# hud_v300_MU.net
KiCad netlist of a schematic drawn in Altium Designer
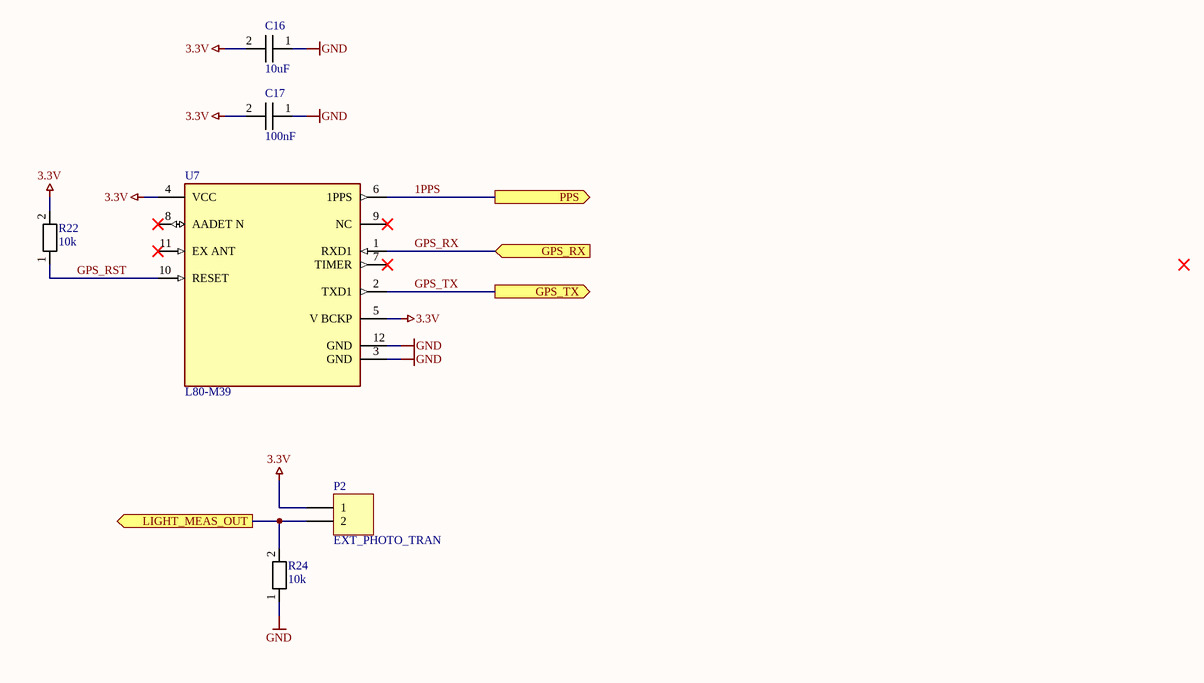
[diagram p0: hud_v300_MU.SchDoc]

(export (version "E")
  (design (tool "Eeschema 10.0.6"))
  (components
    (comp (ref "C16") (value "10uF") (footprint "1210_C") (libsource (lib "Schlib1") (part "CAPACITOR")))
    (comp (ref "C17") (value "100nF") (footprint "0805_C") (libsource (lib "Schlib1") (part "CAPACITOR")))
    (comp (ref "P2")
      (value "EXT_PHOTO_TRAN")
      (footprint "HDR1X2")
      (description "Header, 2-Pin")
      (fields (field (name "PUBLISHER") "Altium Limited"))
      (libsource (lib "Miscellaneous Connectors") (part "Header 2"))
    )
    (comp (ref "R22") (value "10k") (footprint "0805") (libsource (lib "Schlib1") (part "RESISTOR")))
    (comp (ref "R24") (value "10k") (footprint "0805") (libsource (lib "Schlib1") (part "RESISTOR")))
    (comp (ref "U7")
      (value "L80-M39")
      (footprint "L80-M39")
      (description "QUECTEL GPS MODULE")
      (libsource (lib "ic_modules") (part "L80-M39"))
    )
  )
  (nets
    (net (code "1") (name "/1PPS") (class "Default")
      (node (ref "U7") (pin "6") (pinfunction "1PPS_6") (pintype "output"))
    )
    (net (code "2") (name "/GPS_RST") (class "Default")
      (node (ref "R22") (pin "1") (pinfunction "0_1") (pintype "passive"))
      (node (ref "U7") (pin "10") (pinfunction "RESET_10") (pintype "input"))
    )
    (net (code "3") (name "/GPS_RX") (class "Default")
      (node (ref "U7") (pin "1") (pinfunction "RXD1_1") (pintype "input"))
    )
    (net (code "4") (name "/GPS_TX") (class "Default")
      (node (ref "U7") (pin "2") (pinfunction "TXD1_2") (pintype "output"))
    )
    (net (code "5") (name "/LIGHT_MEAS_OUT") (class "Default")
      (node (ref "P2") (pin "2") (pinfunction "2_2") (pintype "passive"))
      (node (ref "R24") (pin "2") (pinfunction "1_2") (pintype "passive"))
    )
    (net (code "6") (name "3.3V") (class "Default")
      (node (ref "C16") (pin "2") (pinfunction "2_2") (pintype "passive"))
      (node (ref "C17") (pin "2") (pinfunction "2_2") (pintype "passive"))
      (node (ref "P2") (pin "1") (pinfunction "1_1") (pintype "passive"))
      (node (ref "R22") (pin "2") (pinfunction "1_2") (pintype "passive"))
      (node (ref "U7") (pin "4") (pinfunction "VCC_4") (pintype "power_in"))
      (node (ref "U7") (pin "5") (pinfunction "V_BCKP_5") (pintype "power_in"))
    )
    (net (code "7") (name "GND") (class "Default")
      (node (ref "C16") (pin "1") (pinfunction "1_1") (pintype "passive"))
      (node (ref "C17") (pin "1") (pinfunction "1_1") (pintype "passive"))
      (node (ref "R24") (pin "1") (pinfunction "0_1") (pintype "passive"))
      (node (ref "U7") (pin "12") (pinfunction "GND_12") (pintype "power_in"))
      (node (ref "U7") (pin "3") (pinfunction "GND_3") (pintype "power_in"))
    )
    (net (code "8") (name "unconnected-(U7-AADET_N-Pad8)") (class "Default")
      (node (ref "U7") (pin "8") (pinfunction "AADET_N_8") (pintype "bidirectional+no_connect"))
    )
    (net (code "9") (name "unconnected-(U7-EX_ANT-Pad11)") (class "Default")
      (node (ref "U7") (pin "11") (pinfunction "EX_ANT_11") (pintype "input+no_connect"))
    )
    (net (code "10") (name "unconnected-(U7-NC-Pad9)") (class "Default")
      (node (ref "U7") (pin "9") (pinfunction "NC_9") (pintype "passive+no_connect"))
    )
    (net (code "11") (name "unconnected-(U7-TIMER-Pad7)") (class "Default")
      (node (ref "U7") (pin "7") (pinfunction "TIMER_7") (pintype "output+no_connect"))
    )
  )
)
